# fonte.net
KiCad netlist of a schematic drawn in Altium Designer
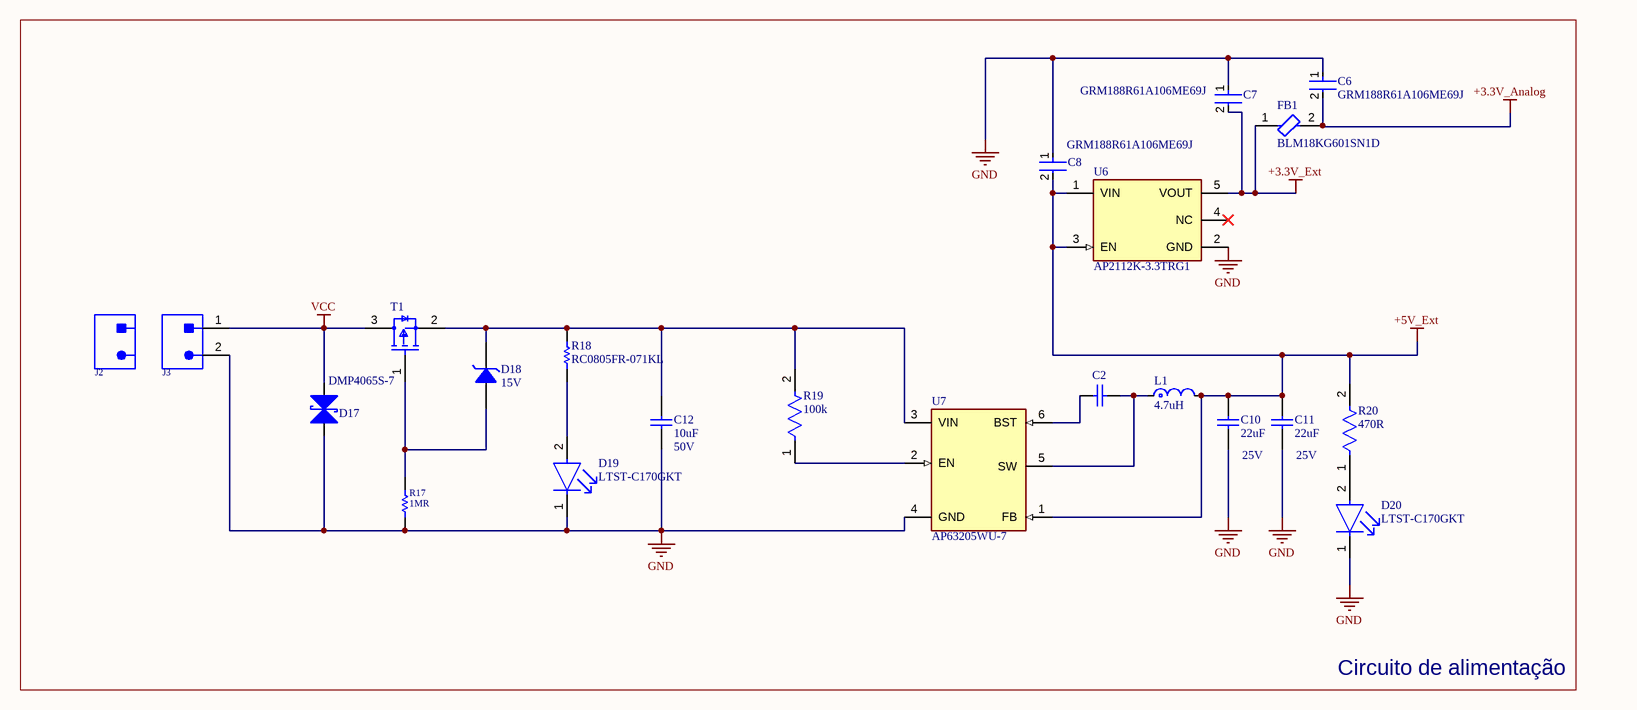
[diagram p0: fonte.SchDoc]

(export (version "E")
  (design (tool "Eeschema 10.0.6"))
  (components
    (comp (ref "C2")
      (value "VJ0603Y104MXJCW1BC")
      (footprint "CAPC1608X95X40NL15T15")
      (fields (field (name "MANUFACTURER") "Vitramon"))
      (libsource (lib "Altium Content Vault") (part "CAP"))
    )
    (comp (ref "C6")
      (value "GRM188R61A106ME69J")
      (footprint "FP-GRM188-0_15-IPC_C")
      (description "Chip Multilayer Ceramic Capacitors for General Purpose, 0603, 10uF, X5R, 15%, 20%, 10V")
      (fields (field (name "TOLERANCE") "20%"))
      (libsource (lib "Altium Content Vault") (part "02cd4be3c70576c341d710602a673aa"))
    )
    (comp (ref "C7")
      (value "GRM188R61A106ME69J")
      (footprint "FP-GRM188-0_15-IPC_C")
      (description "Chip Multilayer Ceramic Capacitors for General Purpose, 0603, 10uF, X5R, 15%, 20%, 10V")
      (fields (field (name "TOLERANCE") "20%"))
      (libsource (lib "Altium Content Vault") (part "02cd4be3c70576c341d710602a673aa"))
    )
    (comp (ref "C8")
      (value "GRM188R61A106ME69J")
      (footprint "FP-GRM188-0_15-IPC_C")
      (description "Chip Multilayer Ceramic Capacitors for General Purpose, 0603, 10uF, X5R, 15%, 20%, 10V")
      (fields (field (name "TOLERANCE") "20%"))
      (libsource (lib "Altium Content Vault") (part "02cd4be3c70576c341d710602a673aa"))
    )
    (comp (ref "C10")
      (value "22uF")
      (footprint "C-0805")
      (description "CAP CER 22UF 25V X5R 0805")
      (fields
        (field (name "MANUFACTURER") "Samsung")
        (field (name "MANUFACTURER PART NUMBER") "CL21A226MAYNNNE")
        (field (name "VOLTAGE RATING (DC)") "25V")
      )
      (libsource (lib "Schlib_Source_IoT") (part "CL21A226MAYNNNE"))
    )
    (comp (ref "C11")
      (value "22uF")
      (footprint "C-0805")
      (description "CAP CER 22UF 25V X5R 0805")
      (fields
        (field (name "MANUFACTURER") "Samsung")
        (field (name "MANUFACTURER PART NUMBER") "CL21A226MAYNNNE")
        (field (name "VOLTAGE RATING") "25V")
      )
      (libsource (lib "Schlib_Source_IoT") (part "CL21A226MAYNNNE"))
    )
    (comp (ref "C12")
      (value "10uF")
      (footprint "C-1206")
      (description "CAP CER 10UF 50V X5R 1206")
      (fields
        (field (name "MANUFACTURER") "Samsung")
        (field (name "MANUFACTURER PART NUMBER") "CL31A106KBHNNNE")
        (field (name "VOLTAGE RATING (DC)") "50V")
      )
      (libsource (lib "Schlib_Source_IoT") (part "CL31A106KBHNNNE"))
    )
    (comp (ref "D17")
      (value "SMBJ28CAQ-13-F")
      (footprint "DO-214AA")
      (description "TVS DIODE 28VWM 45.4VC SMB")
      (fields (field (name "MANUFACTURER") "Diodes"))
      (libsource (lib "Schlib_Source_IoT") (part "SMBJ28CAQ-13-F"))
    )
    (comp (ref "D18")
      (value "MMSZ5245B-TP")
      (footprint "SOD-123")
      (description "DIODE ZENER 15V 500MW SOD123")
      (fields
        (field (name "MANUFACTURER") "MCC")
        (field (name "TOLERANCE") "5%")
        (field (name "ZENER VOLTAGE") "15V")
      )
      (libsource (lib "Schlib_Source_IoT") (part "MMSZ5245B-TP"))
    )
    (comp (ref "D19")
      (value "LTST-C170GKT")
      (footprint "FP-LTST-C170GKT-MFG")
      (description "LED GREEN CLEAR SMD")
      (fields (field (name "VOLTAGE") "5V"))
      (libsource (lib "Altium Content Vault") (part "8706943c75ba83719d021d2fdc84c58"))
    )
    (comp (ref "D20")
      (value "LTST-C170GKT")
      (footprint "FP-LTST-C170GKT-MFG")
      (description "LED GREEN CLEAR SMD")
      (fields (field (name "VOLTAGE") "5V"))
      (libsource (lib "Altium Content Vault") (part "8706943c75ba83719d021d2fdc84c58"))
    )
    (comp (ref "FB1")
      (value "BLM18KG601SN1D")
      (footprint "FP-BLM18-0_15-t0_8-IPC_A")
      (description "Chip Ferrite Bead, 0603, 600Ω @ 100MHz, 0.15Ω, 25%, 1.3A")
      (fields (field (name "TOLERANCE") "25%"))
      (libsource (lib "Altium Content Vault") (part "5f30dd21d616792df468990f7003faa"))
    )
    (comp (ref "J2")
      (value "5447861")
      (footprint "5447861")
      (description "TERM BLOCK PLUG 2POS STR 3.81MM")
      (fields (field (name "MANUFACTURER") "Phoenix Contact") (field (name "VOLTAGE") "300V"))
      (libsource (lib "Schlib_Source_IoT") (part "5447861"))
    )
    (comp (ref "J3")
      (value "5444262")
      (footprint "5444262")
      (description "TERM BLOCK HDR 2POS 90DEG 3.81MM")
      (fields (field (name "MANUFACTURER") "Phoenix Contact") (field (name "VOLTAGE") "300V"))
      (libsource (lib "Schlib_Source_IoT") (part "5444262"))
    )
    (comp (ref "L1")
      (value "4.7uH")
      (footprint "FP-DG6045C-MFG")
      (description "FIXED IND 4.7UH 4A 23 MOHM SMD")
      (fields
        (field (name "MANUFACTURER") "Murata")
        (field (name "MANUFACTURER PART NUMBER") "1255AY-4R7M=P3")
      )
      (libsource (lib "Schlib_Source_IoT") (part "1255AY-4R7M=P3"))
    )
    (comp (ref "R17")
      (value "1MR")
      (footprint "R-0805")
      (description "RES 1M OHM 1% 1/8W 0805")
      (fields
        (field (name "MANUFACTURER") "Yageo")
        (field (name "MANUFACTURER PART NUMBER") "RC0805FR-071ML")
      )
      (libsource (lib "Schlib_Source_IoT") (part "RC0805FR-071ML"))
    )
    (comp (ref "R18")
      (value "RC0805FR-071KL")
      (footprint "RESC2013X60X35ML10T20")
      (description "Chip Resistor, 1 KOhm, +/- 1%, 125 mW, -55 to 155 degC, 0805 (2012 Metric), RoHS, Tape and Reel")
      (fields (field (name "TOLERANCE") "1%") (field (name "MANUFACTURER") "Yageo"))
      (libsource (lib "Altium Content Vault") (part "RES-2"))
    )
    (comp (ref "R19")
      (value "100k")
      (footprint "FP-CRGCQ0805-IPC_C")
      (description "CRGCQ 0805 100K 1%")
      (fields
        (field (name "MANUFACTURER") "TE Connectivity")
        (field (name "OCTOPART") "https://octopart.com/crgcq0805f100k-te+connectivity-91018138")
      )
      (libsource (lib "Altium Content Vault") (part "1029c3af85768c4190bb7ad29bc67b5"))
    )
    (comp (ref "R20")
      (value "470R")
      (footprint "FP-CRGCQ0805-IPC_C")
      (description "CRGCQ0805 470Ω 0.125W ±100ppm/°C 5% 150V")
      (fields (field (name "TOLERANCE") "0.05") (field (name "MANUFACTURER") "TE Connectivity"))
      (libsource (lib "Altium Content Vault") (part "1029c3af85768c4190bb7ad29bc67b5"))
    )
    (comp (ref "T1")
      (value "DMP4065S-7")
      (footprint "FP-SOT23-MFG")
      (description "MOSFET P-CH 40V 2.4A SOT23")
      (fields
        (field (name "MANUFACTURER") "Diodes Inc.")
        (field (name "OCTOPART") "https://octopart.com/dmp4065s-7-diodes+inc.-57605044")
      )
      (libsource (lib "Altium Content Vault") (part "90d26376f95f59a583a7107ec0b7fdb"))
    )
    (comp (ref "U6")
      (value "AP2112K-3.3TRG1")
      (footprint "FP-SOT25-IPC_A")
      (description "IC REG LINEAR 3.3V 600MA SOT25")
      (libsource (lib "Altium Content Vault") (part "c8ab751aee5229183125ab046a11caa"))
    )
    (comp (ref "U7")
      (value "AP63205WU-7")
      (footprint "TSOT-23-6_A")
      (description "IC REG BUCK 5V 2A TSOT23-6")
      (fields (field (name "MANUFACTURER") "Diodes"))
      (libsource (lib "Schlib_Source_IoT") (part "AP63205WU-7"))
    )
  )
  (nets
    (net (code "1") (name "+3.3V_Analog") (class "Default")
      (node (ref "C6") (pin "2") (pinfunction "2_2") (pintype "passive"))
      (node (ref "FB1") (pin "2") (pinfunction "2_2") (pintype "passive"))
    )
    (net (code "2") (name "+3.3V_Ext") (class "Default")
      (node (ref "C7") (pin "2") (pinfunction "2_2") (pintype "passive"))
      (node (ref "FB1") (pin "1") (pinfunction "1_1") (pintype "passive"))
      (node (ref "U6") (pin "5") (pinfunction "VOUT_5") (pintype "power_in"))
    )
    (net (code "3") (name "+5V_Ext") (class "Default")
      (node (ref "C10") (pin "1") (pinfunction "1_1") (pintype "passive"))
      (node (ref "C11") (pin "1") (pinfunction "1_1") (pintype "passive"))
      (node (ref "C8") (pin "2") (pinfunction "2_2") (pintype "passive"))
      (node (ref "L1") (pin "2") (pinfunction "2_2") (pintype "passive"))
      (node (ref "R20") (pin "2") (pinfunction "2_2") (pintype "passive"))
      (node (ref "U6") (pin "1") (pinfunction "VIN_1") (pintype "power_in"))
      (node (ref "U6") (pin "3") (pinfunction "EN_3") (pintype "input"))
      (node (ref "U7") (pin "1") (pinfunction "FB_1") (pintype "input"))
    )
    (net (code "4") (name "GND") (class "Default")
      (node (ref "C10") (pin "2") (pinfunction "2_2") (pintype "passive"))
      (node (ref "C11") (pin "2") (pinfunction "2_2") (pintype "passive"))
      (node (ref "C12") (pin "2") (pinfunction "2_2") (pintype "passive"))
      (node (ref "C6") (pin "1") (pinfunction "1_1") (pintype "passive"))
      (node (ref "C7") (pin "1") (pinfunction "1_1") (pintype "passive"))
      (node (ref "C8") (pin "1") (pinfunction "1_1") (pintype "passive"))
      (node (ref "D17") (pin "2") (pinfunction "Anode_2") (pintype "passive"))
      (node (ref "D19") (pin "1") (pinfunction "C_1") (pintype "passive"))
      (node (ref "D20") (pin "1") (pinfunction "C_1") (pintype "passive"))
      (node (ref "J3") (pin "2") (pinfunction "2_2") (pintype "passive"))
      (node (ref "R17") (pin "1") (pinfunction "1_1") (pintype "passive"))
      (node (ref "U6") (pin "2") (pinfunction "GND_2") (pintype "power_in"))
      (node (ref "U7") (pin "4") (pinfunction "GND_4") (pintype "power_in"))
    )
    (net (code "5") (name "Net-(D18-A)") (class "Default")
      (node (ref "D18") (pin "2") (pinfunction "A_2") (pintype "passive"))
      (node (ref "R17") (pin "2") (pinfunction "2_2") (pintype "passive"))
      (node (ref "T1") (pin "1") (pinfunction "G_1") (pintype "passive"))
    )
    (net (code "6") (name "Net-(D18-K)") (class "Default")
      (node (ref "C12") (pin "1") (pinfunction "1_1") (pintype "passive"))
      (node (ref "D18") (pin "1") (pinfunction "K_1") (pintype "passive"))
      (node (ref "R18") (pin "2") (pinfunction "2_2") (pintype "passive"))
      (node (ref "R19") (pin "2") (pinfunction "2_2") (pintype "passive"))
      (node (ref "T1") (pin "2") (pinfunction "S_2") (pintype "passive"))
      (node (ref "U7") (pin "3") (pinfunction "VIN_3") (pintype "power_in"))
    )
    (net (code "7") (name "Net-(D19-A)") (class "Default")
      (node (ref "D19") (pin "2") (pinfunction "A_2") (pintype "passive"))
      (node (ref "R18") (pin "1") (pinfunction "1_1") (pintype "passive"))
    )
    (net (code "8") (name "Net-(D20-A)") (class "Default")
      (node (ref "D20") (pin "2") (pinfunction "A_2") (pintype "passive"))
      (node (ref "R20") (pin "1") (pinfunction "1_1") (pintype "passive"))
    )
    (net (code "9") (name "Net-(U7-BST)") (class "Default")
      (node (ref "C2") (pin "1") (pinfunction "1_1") (pintype "passive"))
      (node (ref "U7") (pin "6") (pinfunction "BST_6") (pintype "input"))
    )
    (net (code "10") (name "Net-(U7-EN)") (class "Default")
      (node (ref "R19") (pin "1") (pinfunction "1_1") (pintype "passive"))
      (node (ref "U7") (pin "2") (pinfunction "EN_2") (pintype "input"))
    )
    (net (code "11") (name "Net-(U7-SW)") (class "Default")
      (node (ref "C2") (pin "2") (pinfunction "2_2") (pintype "passive"))
      (node (ref "L1") (pin "1") (pinfunction "1_1") (pintype "passive"))
      (node (ref "U7") (pin "5") (pinfunction "SW_5") (pintype "power_in"))
    )
    (net (code "12") (name "VCC") (class "Default")
      (node (ref "D17") (pin "1") (pinfunction "Cathode_1") (pintype "passive"))
      (node (ref "J3") (pin "1") (pinfunction "1_1") (pintype "passive"))
      (node (ref "T1") (pin "3") (pinfunction "D_3") (pintype "passive"))
    )
    (net (code "13") (name "unconnected-(U6-NC-Pad4)") (class "Default")
      (node (ref "U6") (pin "4") (pinfunction "NC_4") (pintype "passive+no_connect"))
    )
  )
)
